# Peripheral.net
KiCad netlist of a schematic drawn in Altium Designer
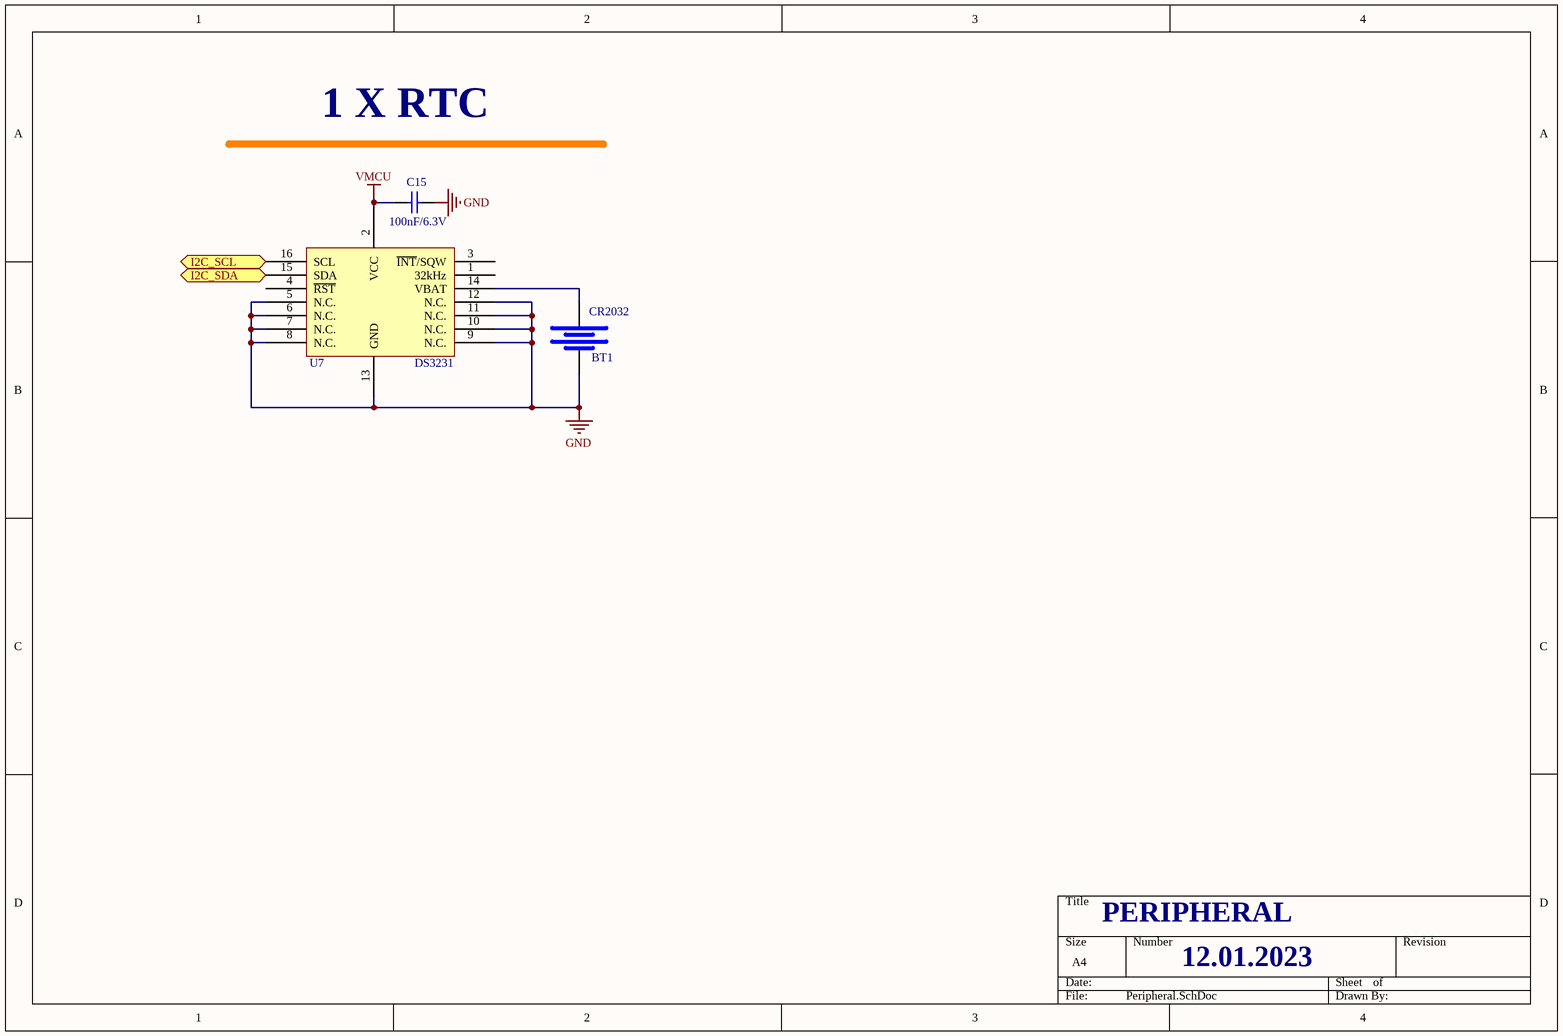
[diagram p0: Peripheral.SchDoc]

(export (version "E")
  (design (tool "Eeschema 10.0.6"))
  (components
    (comp (ref "BT1")
      (value "CR2032")
      (footprint "CR2032")
      (description "BATTERY CR2032 HORIZONTAL 3PIN")
      (libsource (lib "geolib") (part "BATTERY_CR2032"))
    )
    (comp (ref "C15")
      (value "100nF/6.3V")
      (footprint "CAP0603W")
      (description "CAPACITOR 0603 Case")
      (fields (field (name "PUBLISHER") "Altium Limited"))
      (libsource (lib "geolib") (part "CAP1"))
    )
    (comp (ref "U7")
      (value "DS3231")
      (footprint "SOIC16")
      (description "IC DS3231SN RTC W/TCXO 16-SOIC MAXIM")
      (libsource (lib "geolib") (part "RTC_DS3231"))
    )
  )
  (nets
    (net (code "1") (name "/I2C_SCL") (class "Default")
      (node (ref "U7") (pin "16") (pinfunction "SCL_16") (pintype "passive"))
    )
    (net (code "2") (name "/I2C_SDA") (class "Default")
      (node (ref "U7") (pin "15") (pinfunction "SDA_15") (pintype "passive"))
    )
    (net (code "3") (name "GND") (class "Default")
      (node (ref "BT1") (pin "2") (pinfunction "-_2") (pintype "passive"))
      (node (ref "C15") (pin "2") (pinfunction "2_2") (pintype "passive"))
      (node (ref "U7") (pin "10") (pinfunction "N.C._10") (pintype "passive"))
      (node (ref "U7") (pin "11") (pinfunction "N.C._11") (pintype "passive"))
      (node (ref "U7") (pin "12") (pinfunction "N.C._12") (pintype "passive"))
      (node (ref "U7") (pin "13") (pinfunction "GND_13") (pintype "passive"))
      (node (ref "U7") (pin "5") (pinfunction "N.C._5") (pintype "passive"))
      (node (ref "U7") (pin "6") (pinfunction "N.C._6") (pintype "passive"))
      (node (ref "U7") (pin "7") (pinfunction "N.C._7") (pintype "passive"))
      (node (ref "U7") (pin "8") (pinfunction "N.C._8") (pintype "passive"))
      (node (ref "U7") (pin "9") (pinfunction "N.C._9") (pintype "passive"))
    )
    (net (code "4") (name "Net-(BT1-+)") (class "Default")
      (node (ref "BT1") (pin "1") (pinfunction "+_1") (pintype "passive"))
      (node (ref "U7") (pin "14") (pinfunction "VBAT_14") (pintype "passive"))
    )
    (net (code "5") (name "VMCU") (class "Default")
      (node (ref "C15") (pin "1") (pinfunction "1_1") (pintype "passive"))
      (node (ref "U7") (pin "2") (pinfunction "VCC_2") (pintype "passive"))
    )
    (net (code "6") (name "unconnected-(U7-32kHz-Pad1)") (class "Default")
      (node (ref "U7") (pin "1") (pinfunction "32kHz_1") (pintype "passive"))
    )
    (net (code "7") (name "unconnected-(U7-~{INT}{slash}SQW-Pad3)") (class "Default")
      (node (ref "U7") (pin "3") (pinfunction "~{INT}/SQW_3") (pintype "passive"))
    )
    (net (code "8") (name "unconnected-(U7-~{RST}-Pad4)") (class "Default")
      (node (ref "U7") (pin "4") (pinfunction "~{RST}_4") (pintype "passive"))
    )
  )
)
